# ProPrj___2026-01-25.net
KiCad netlist of a schematic drawn in EasyEDA Pro
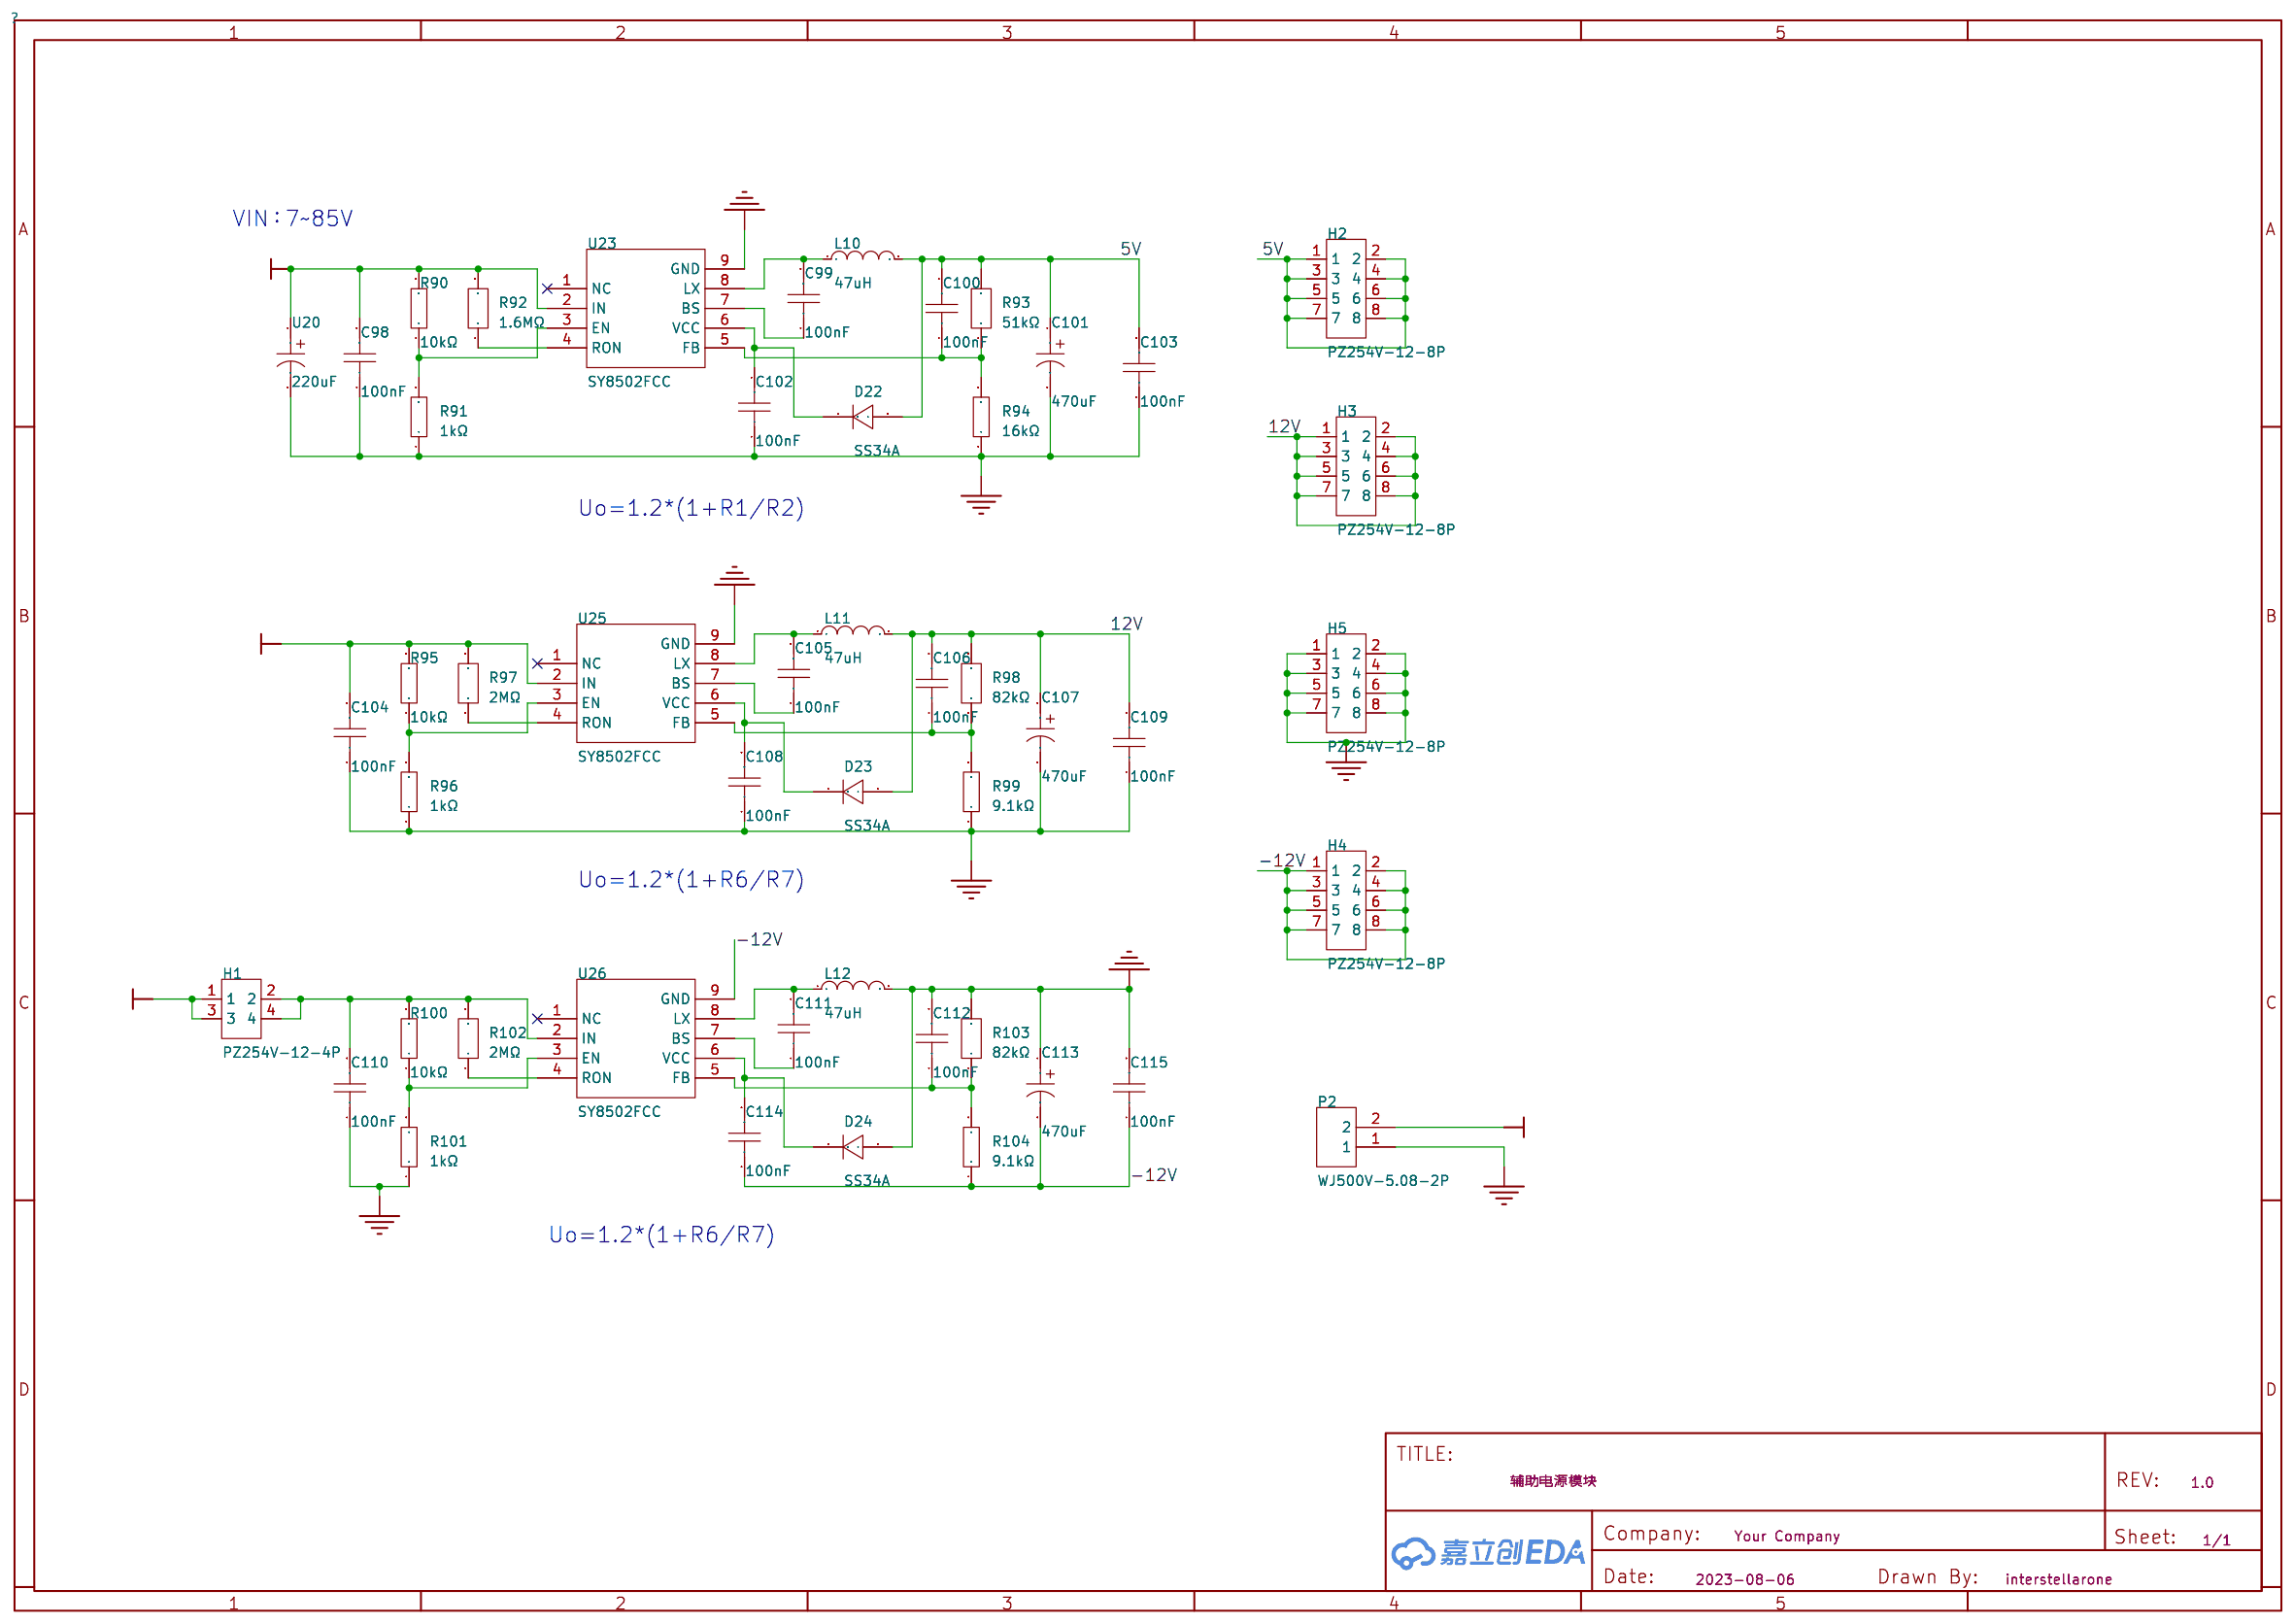
[diagram p0: schematic sheet]

(export (version "E")
  (design (tool "Eeschema 10.0.6"))
  (components
    (comp (ref "C98")
      (value "100nF")
      (footprint "easyedapro:C0603")
      (description "容值:100nF;精度:±10%;额定电压:50V;温度系数:X7R;")
      (fields
        (field (name "Manufacturer Part") "CGA0603X7R104K500JT")
        (field (name "Manufacturer") "HRE(芯声)")
      )
      (libsource (lib "easyedapro") (part "CGA0603X7R104K500JT"))
    )
    (comp (ref "C99")
      (value "100nF")
      (footprint "easyedapro:C0603")
      (description "容值:100nF;精度:±10%;额定电压:50V;温度系数:X7R;")
      (fields
        (field (name "Manufacturer Part") "CGA0603X7R104K500JT")
        (field (name "Manufacturer") "HRE(芯声)")
      )
      (libsource (lib "easyedapro") (part "CGA0603X7R104K500JT"))
    )
    (comp (ref "C100")
      (value "100nF")
      (footprint "easyedapro:C0603")
      (description "容值:100nF;精度:±10%;额定电压:50V;温度系数:X7R;")
      (fields
        (field (name "Manufacturer Part") "CGA0603X7R104K500JT")
        (field (name "Manufacturer") "HRE(芯声)")
      )
      (libsource (lib "easyedapro") (part "CGA0603X7R104K500JT"))
    )
    (comp (ref "C101")
      (value "470uF")
      (footprint "easyedapro:CAP-TH_BD6.0-P2.50-D0.5-FD")
      (description "容值:470uF;额定电压:10V;")
      (fields
        (field (name "Manufacturer Part") "CD110477M1A0607VFL")
        (field (name "Manufacturer") "HRK(鸿瑞凯电子)")
      )
      (libsource (lib "easyedapro") (part "CD110477M1A0607VFL"))
    )
    (comp (ref "C102")
      (value "100nF")
      (footprint "easyedapro:C0603")
      (description "容值:100nF;精度:±10%;额定电压:50V;温度系数:X7R;")
      (fields
        (field (name "Manufacturer Part") "CGA0603X7R104K500JT")
        (field (name "Manufacturer") "HRE(芯声)")
      )
      (libsource (lib "easyedapro") (part "CGA0603X7R104K500JT"))
    )
    (comp (ref "C103")
      (value "100nF")
      (footprint "easyedapro:C0603")
      (description "容值:100nF;精度:±10%;额定电压:50V;温度系数:X7R;")
      (fields
        (field (name "Manufacturer Part") "CGA0603X7R104K500JT")
        (field (name "Manufacturer") "HRE(芯声)")
      )
      (libsource (lib "easyedapro") (part "CGA0603X7R104K500JT"))
    )
    (comp (ref "C104")
      (value "100nF")
      (footprint "easyedapro:C0603")
      (description "容值:100nF;精度:±10%;额定电压:50V;温度系数:X7R;")
      (fields
        (field (name "Manufacturer Part") "CGA0603X7R104K500JT")
        (field (name "Manufacturer") "HRE(芯声)")
      )
      (libsource (lib "easyedapro") (part "CGA0603X7R104K500JT"))
    )
    (comp (ref "C105")
      (value "100nF")
      (footprint "easyedapro:C0603")
      (description "容值:100nF;精度:±10%;额定电压:50V;温度系数:X7R;")
      (fields
        (field (name "Manufacturer Part") "CGA0603X7R104K500JT")
        (field (name "Manufacturer") "HRE(芯声)")
      )
      (libsource (lib "easyedapro") (part "CGA0603X7R104K500JT"))
    )
    (comp (ref "C106")
      (value "100nF")
      (footprint "easyedapro:C0603")
      (description "容值:100nF;精度:±10%;额定电压:50V;温度系数:X7R;")
      (fields
        (field (name "Manufacturer Part") "CGA0603X7R104K500JT")
        (field (name "Manufacturer") "HRE(芯声)")
      )
      (libsource (lib "easyedapro") (part "CGA0603X7R104K500JT"))
    )
    (comp (ref "C107")
      (value "470uF")
      (footprint "easyedapro:CAP-TH_BD6.0-P2.50-D0.5-FD")
      (description "容值:470uF;额定电压:10V;")
      (fields
        (field (name "Manufacturer Part") "CD110477M1A0607VFL")
        (field (name "Manufacturer") "HRK(鸿瑞凯电子)")
      )
      (libsource (lib "easyedapro") (part "CD110477M1A0607VFL"))
    )
    (comp (ref "C108")
      (value "100nF")
      (footprint "easyedapro:C0603")
      (description "容值:100nF;精度:±10%;额定电压:50V;温度系数:X7R;")
      (fields
        (field (name "Manufacturer Part") "CGA0603X7R104K500JT")
        (field (name "Manufacturer") "HRE(芯声)")
      )
      (libsource (lib "easyedapro") (part "CGA0603X7R104K500JT"))
    )
    (comp (ref "C109")
      (value "100nF")
      (footprint "easyedapro:C0603")
      (description "容值:100nF;精度:±10%;额定电压:50V;温度系数:X7R;")
      (fields
        (field (name "Manufacturer Part") "CGA0603X7R104K500JT")
        (field (name "Manufacturer") "HRE(芯声)")
      )
      (libsource (lib "easyedapro") (part "CGA0603X7R104K500JT"))
    )
    (comp (ref "C110")
      (value "100nF")
      (footprint "easyedapro:C0603")
      (description "容值:100nF;精度:±10%;额定电压:50V;温度系数:X7R;")
      (fields
        (field (name "Manufacturer Part") "CGA0603X7R104K500JT")
        (field (name "Manufacturer") "HRE(芯声)")
      )
      (libsource (lib "easyedapro") (part "CGA0603X7R104K500JT"))
    )
    (comp (ref "C111")
      (value "100nF")
      (footprint "easyedapro:C0603")
      (description "容值:100nF;精度:±10%;额定电压:50V;温度系数:X7R;")
      (fields
        (field (name "Manufacturer Part") "CGA0603X7R104K500JT")
        (field (name "Manufacturer") "HRE(芯声)")
      )
      (libsource (lib "easyedapro") (part "CGA0603X7R104K500JT"))
    )
    (comp (ref "C112")
      (value "100nF")
      (footprint "easyedapro:C0603")
      (description "容值:100nF;精度:±10%;额定电压:50V;温度系数:X7R;")
      (fields
        (field (name "Manufacturer Part") "CGA0603X7R104K500JT")
        (field (name "Manufacturer") "HRE(芯声)")
      )
      (libsource (lib "easyedapro") (part "CGA0603X7R104K500JT"))
    )
    (comp (ref "C113")
      (value "470uF")
      (footprint "easyedapro:CAP-TH_BD6.0-P2.50-D0.5-FD")
      (description "容值:470uF;额定电压:10V;")
      (fields
        (field (name "Manufacturer Part") "CD110477M1A0607VFL")
        (field (name "Manufacturer") "HRK(鸿瑞凯电子)")
      )
      (libsource (lib "easyedapro") (part "CD110477M1A0607VFL"))
    )
    (comp (ref "C114")
      (value "100nF")
      (footprint "easyedapro:C0603")
      (description "容值:100nF;精度:±10%;额定电压:50V;温度系数:X7R;")
      (fields
        (field (name "Manufacturer Part") "CGA0603X7R104K500JT")
        (field (name "Manufacturer") "HRE(芯声)")
      )
      (libsource (lib "easyedapro") (part "CGA0603X7R104K500JT"))
    )
    (comp (ref "C115")
      (value "100nF")
      (footprint "easyedapro:C0603")
      (description "容值:100nF;精度:±10%;额定电压:50V;温度系数:X7R;")
      (fields
        (field (name "Manufacturer Part") "CGA0603X7R104K500JT")
        (field (name "Manufacturer") "HRE(芯声)")
      )
      (libsource (lib "easyedapro") (part "CGA0603X7R104K500JT"))
    )
    (comp (ref "D22")
      (value "SS34A")
      (footprint "easyedapro:SMA_L4.3-W2.6-LS5.2-RD")
      (description "正向压降(Vf):500mV@3A;直流反向耐压(Vr):40V;整流电流:3A;")
      (fields (field (name "Manufacturer") "YANGJIE(扬杰)"))
      (libsource (lib "easyedapro") (part "SS34A"))
    )
    (comp (ref "D23")
      (value "SS34A")
      (footprint "easyedapro:SMA_L4.3-W2.6-LS5.2-RD")
      (description "正向压降(Vf):500mV@3A;直流反向耐压(Vr):40V;整流电流:3A;")
      (fields (field (name "Manufacturer") "YANGJIE(扬杰)"))
      (libsource (lib "easyedapro") (part "SS34A"))
    )
    (comp (ref "D24")
      (value "SS34A")
      (footprint "easyedapro:SMA_L4.3-W2.6-LS5.2-RD")
      (description "正向压降(Vf):500mV@3A;直流反向耐压(Vr):40V;整流电流:3A;")
      (fields (field (name "Manufacturer") "YANGJIE(扬杰)"))
      (libsource (lib "easyedapro") (part "SS34A"))
    )
    (comp (ref "H1")
      (value "PZ254V-12-4P")
      (footprint "easyedapro:HDR-TH_4P-P2.54-V-M-R2-C2-S2.54")
      (fields (field (name "Manufacturer") "XFCN(兴飞)"))
      (libsource (lib "easyedapro") (part "PZ254V-12-4P"))
    )
    (comp (ref "H2")
      (value "PZ254V-12-8P")
      (footprint "easyedapro:HDR-TH_8P-P2.54-V-M-R2-C4-S2.54")
      (fields (field (name "Manufacturer") "XFCN(兴飞)"))
      (libsource (lib "easyedapro") (part "PZ254V-12-8P"))
    )
    (comp (ref "H3")
      (value "PZ254V-12-8P")
      (footprint "easyedapro:HDR-TH_8P-P2.54-V-M-R2-C4-S2.54")
      (fields (field (name "Manufacturer") "XFCN(兴飞)"))
      (libsource (lib "easyedapro") (part "PZ254V-12-8P"))
    )
    (comp (ref "H4")
      (value "PZ254V-12-8P")
      (footprint "easyedapro:HDR-TH_8P-P2.54-V-M-R2-C4-S2.54")
      (fields (field (name "Manufacturer") "XFCN(兴飞)"))
      (libsource (lib "easyedapro") (part "PZ254V-12-8P"))
    )
    (comp (ref "H5")
      (value "PZ254V-12-8P")
      (footprint "easyedapro:HDR-TH_8P-P2.54-V-M-R2-C4-S2.54")
      (fields (field (name "Manufacturer") "XFCN(兴飞)"))
      (libsource (lib "easyedapro") (part "PZ254V-12-8P"))
    )
    (comp (ref "L10")
      (value "47uH")
      (footprint "easyedapro:IND-SMD_L7.0-W6.6_FXL0630")
      (description "电感值:47uH;精度:±20%;额定电流:1.5A;饱和电流(Isat):2A;类型:一体成型电感;")
      (fields (field (name "Manufacturer Part") "FXL0630-470-M") (field (name "Manufacturer") "cjiang(长江微电)"))
      (libsource (lib "easyedapro") (part "FXL0630-470-M"))
    )
    (comp (ref "L11")
      (value "47uH")
      (footprint "easyedapro:IND-SMD_L7.0-W6.6_FXL0630")
      (description "电感值:47uH;精度:±20%;额定电流:1.5A;饱和电流(Isat):2A;类型:一体成型电感;")
      (fields (field (name "Manufacturer Part") "FXL0630-470-M") (field (name "Manufacturer") "cjiang(长江微电)"))
      (libsource (lib "easyedapro") (part "FXL0630-470-M"))
    )
    (comp (ref "L12")
      (value "47uH")
      (footprint "easyedapro:IND-SMD_L7.0-W6.6_FXL0630")
      (description "电感值:47uH;精度:±20%;额定电流:1.5A;饱和电流(Isat):2A;类型:一体成型电感;")
      (fields (field (name "Manufacturer Part") "FXL0630-470-M") (field (name "Manufacturer") "cjiang(长江微电)"))
      (libsource (lib "easyedapro") (part "FXL0630-470-M"))
    )
    (comp (ref "P2")
      (value "WJ500V-5.08-2P")
      (footprint "easyedapro:CONN-TH_2P-P5.00_WJ500V-5.08-2P")
      (fields (field (name "Manufacturer") "KANGNEX(康奈克斯电气)"))
      (libsource (lib "easyedapro") (part "WJ500V-5.08-2P-14-00A"))
    )
    (comp (ref "R90")
      (value "10kΩ")
      (footprint "easyedapro:R0603")
      (description "电阻类型:厚膜电阻;阻值:10kΩ;精度:±1%;功率:100mW;最大工作电压:75V;温度系数:±100ppm/°C;")
      (fields
        (field (name "Manufacturer Part") "0603WAF1002T5E")
        (field (name "Manufacturer") "UNI-ROYAL(厚声)")
      )
      (libsource (lib "easyedapro") (part "0603WAF1002T5E"))
    )
    (comp (ref "R91")
      (value "1kΩ")
      (footprint "easyedapro:R0603")
      (description "电阻类型:厚膜电阻;阻值:1kΩ;精度:±1%;功率:100mW;最大工作电压:75V;温度系数:±100ppm/°C;")
      (fields
        (field (name "Manufacturer Part") "0603WAF1001T5E")
        (field (name "Manufacturer") "UNI-ROYAL(厚声)")
      )
      (libsource (lib "easyedapro") (part "0603WAF1001T5E"))
    )
    (comp (ref "R92")
      (value "1.6MΩ")
      (footprint "easyedapro:R0603")
      (description "电阻类型:厚膜电阻;阻值:1.6MΩ;精度:±5%;功率:100mW;最大工作电压:75V;温度系数:±100ppm/°C;")
      (fields (field (name "Manufacturer Part") "FRC0603J165 TS") (field (name "Manufacturer") "FOJAN(富捷)"))
      (libsource (lib "easyedapro") (part "FRC0603J165 TS"))
    )
    (comp (ref "R93")
      (value "51kΩ")
      (footprint "easyedapro:R0603")
      (description "电阻类型:厚膜电阻;阻值:51kΩ;精度:±1%;功率:100mW;最大工作电压:75V;温度系数:±100ppm/°C;")
      (fields (field (name "Manufacturer Part") "FRC0603F5102TS") (field (name "Manufacturer") "FOJAN(富捷)"))
      (libsource (lib "easyedapro") (part "FRC0603F5102TS"))
    )
    (comp (ref "R94")
      (value "16kΩ")
      (footprint "easyedapro:R0603")
      (description "电阻类型:厚膜电阻;阻值:16kΩ;精度:±1%;功率:100mW;最大工作电压:75V;温度系数:±100ppm/°C;")
      (fields
        (field (name "Manufacturer Part") "0603WAF1602T5E")
        (field (name "Manufacturer") "UNI-ROYAL(厚声)")
      )
      (libsource (lib "easyedapro") (part "16KΩ(1602) ±1%"))
    )
    (comp (ref "R95")
      (value "10kΩ")
      (footprint "easyedapro:R0603")
      (description "电阻类型:厚膜电阻;阻值:10kΩ;精度:±1%;功率:100mW;最大工作电压:75V;温度系数:±100ppm/°C;")
      (fields
        (field (name "Manufacturer Part") "0603WAF1002T5E")
        (field (name "Manufacturer") "UNI-ROYAL(厚声)")
      )
      (libsource (lib "easyedapro") (part "0603WAF1002T5E"))
    )
    (comp (ref "R96")
      (value "1kΩ")
      (footprint "easyedapro:R0603")
      (description "电阻类型:厚膜电阻;阻值:1kΩ;精度:±1%;功率:100mW;最大工作电压:75V;温度系数:±100ppm/°C;")
      (fields
        (field (name "Manufacturer Part") "0603WAF1001T5E")
        (field (name "Manufacturer") "UNI-ROYAL(厚声)")
      )
      (libsource (lib "easyedapro") (part "0603WAF1001T5E"))
    )
    (comp (ref "R97")
      (value "2MΩ")
      (footprint "easyedapro:R0603")
      (description "电阻类型:厚膜电阻;阻值:1.6MΩ;精度:±5%;功率:100mW;最大工作电压:75V;温度系数:±100ppm/°C;")
      (fields (field (name "Manufacturer Part") "FRC0603J165 TS") (field (name "Manufacturer") "FOJAN(富捷)"))
      (libsource (lib "easyedapro") (part "FRC0603J165 TS"))
    )
    (comp (ref "R98")
      (value "82kΩ")
      (footprint "easyedapro:R0603")
      (description "电阻类型:厚膜电阻;阻值:51kΩ;精度:±1%;功率:100mW;最大工作电压:75V;温度系数:±100ppm/°C;")
      (fields (field (name "Manufacturer Part") "FRC0603F5102TS") (field (name "Manufacturer") "FOJAN(富捷)"))
      (libsource (lib "easyedapro") (part "FRC0603F5102TS"))
    )
    (comp (ref "R99")
      (value "9.1kΩ")
      (footprint "easyedapro:R0603")
      (description "电阻类型:厚膜电阻;阻值:16kΩ;精度:±1%;功率:100mW;最大工作电压:75V;温度系数:±100ppm/°C;")
      (fields
        (field (name "Manufacturer Part") "0603WAF1602T5E")
        (field (name "Manufacturer") "UNI-ROYAL(厚声)")
      )
      (libsource (lib "easyedapro") (part "16KΩ(1602) ±1%"))
    )
    (comp (ref "R100")
      (value "10kΩ")
      (footprint "easyedapro:R0603")
      (description "电阻类型:厚膜电阻;阻值:10kΩ;精度:±1%;功率:100mW;最大工作电压:75V;温度系数:±100ppm/°C;")
      (fields
        (field (name "Manufacturer Part") "0603WAF1002T5E")
        (field (name "Manufacturer") "UNI-ROYAL(厚声)")
      )
      (libsource (lib "easyedapro") (part "0603WAF1002T5E"))
    )
    (comp (ref "R101")
      (value "1kΩ")
      (footprint "easyedapro:R0603")
      (description "电阻类型:厚膜电阻;阻值:1kΩ;精度:±1%;功率:100mW;最大工作电压:75V;温度系数:±100ppm/°C;")
      (fields
        (field (name "Manufacturer Part") "0603WAF1001T5E")
        (field (name "Manufacturer") "UNI-ROYAL(厚声)")
      )
      (libsource (lib "easyedapro") (part "0603WAF1001T5E"))
    )
    (comp (ref "R102")
      (value "2MΩ")
      (footprint "easyedapro:R0603")
      (description "电阻类型:厚膜电阻;阻值:1.6MΩ;精度:±5%;功率:100mW;最大工作电压:75V;温度系数:±100ppm/°C;")
      (fields (field (name "Manufacturer Part") "FRC0603J165 TS") (field (name "Manufacturer") "FOJAN(富捷)"))
      (libsource (lib "easyedapro") (part "FRC0603J165 TS"))
    )
    (comp (ref "R103")
      (value "82kΩ")
      (footprint "easyedapro:R0603")
      (description "电阻类型:厚膜电阻;阻值:51kΩ;精度:±1%;功率:100mW;最大工作电压:75V;温度系数:±100ppm/°C;")
      (fields (field (name "Manufacturer Part") "FRC0603F5102TS") (field (name "Manufacturer") "FOJAN(富捷)"))
      (libsource (lib "easyedapro") (part "FRC0603F5102TS"))
    )
    (comp (ref "R104")
      (value "9.1kΩ")
      (footprint "easyedapro:R0603")
      (description "电阻类型:厚膜电阻;阻值:16kΩ;精度:±1%;功率:100mW;最大工作电压:75V;温度系数:±100ppm/°C;")
      (fields
        (field (name "Manufacturer Part") "0603WAF1602T5E")
        (field (name "Manufacturer") "UNI-ROYAL(厚声)")
      )
      (libsource (lib "easyedapro") (part "16KΩ(1602) ±1%"))
    )
    (comp (ref "U20")
      (value "220uF")
      (footprint "easyedapro:CAP-TH_BD12.5-P5.00-D0.6-FD")
      (description "容值:220uF;精度:±20%;额定电压:100V;")
      (fields (field (name "Manufacturer Part") "ERJ1KM221W20OT") (field (name "Manufacturer") "AISHI(艾华集团)"))
      (libsource (lib "easyedapro") (part "ERJ1KM221W20OT"))
    )
    (comp (ref "U23")
      (value "SY8502FCC")
      (footprint "easyedapro:SOIC-8_L4.9-W3.9-P1.27-LS6.0-BL-EP")
      (description "功能类型:降压型;输出类型:固定;工作电压:7V~85V;输出电压:5V;输出电流:1.2A;")
      (fields (field (name "Manufacturer") "silergy(矽力杰)"))
      (libsource (lib "easyedapro") (part "SY8502FCC"))
    )
    (comp (ref "U25")
      (value "SY8502FCC")
      (footprint "easyedapro:SOIC-8_L4.9-W3.9-P1.27-LS6.0-BL-EP")
      (description "功能类型:降压型;输出类型:固定;工作电压:7V~85V;输出电压:5V;输出电流:1.2A;")
      (fields (field (name "Manufacturer") "silergy(矽力杰)"))
      (libsource (lib "easyedapro") (part "SY8502FCC"))
    )
    (comp (ref "U26")
      (value "SY8502FCC")
      (footprint "easyedapro:SOIC-8_L4.9-W3.9-P1.27-LS6.0-BL-EP")
      (description "功能类型:降压型;输出类型:固定;工作电压:7V~85V;输出电压:5V;输出电流:1.2A;")
      (fields (field (name "Manufacturer") "silergy(矽力杰)"))
      (libsource (lib "easyedapro") (part "SY8502FCC"))
    )
  )
  (nets
    (net (code "1") (name "/-12V") (class "Default")
      (node (ref "C113") (pin "2") (pinfunction "2_2") (pintype "input"))
      (node (ref "C114") (pin "1") (pinfunction "1_1") (pintype "unspecified"))
      (node (ref "C115") (pin "1") (pinfunction "1_1") (pintype "unspecified"))
      (node (ref "H4") (pin "1") (pinfunction "1_1") (pintype "unspecified"))
      (node (ref "H4") (pin "2") (pinfunction "2_2") (pintype "unspecified"))
      (node (ref "H4") (pin "3") (pinfunction "3_3") (pintype "unspecified"))
      (node (ref "H4") (pin "4") (pinfunction "4_4") (pintype "unspecified"))
      (node (ref "H4") (pin "5") (pinfunction "5_5") (pintype "unspecified"))
      (node (ref "H4") (pin "6") (pinfunction "6_6") (pintype "unspecified"))
      (node (ref "H4") (pin "7") (pinfunction "7_7") (pintype "unspecified"))
      (node (ref "H4") (pin "8") (pinfunction "8_8") (pintype "unspecified"))
      (node (ref "R104") (pin "1") (pinfunction "1_1") (pintype "unspecified"))
      (node (ref "U26") (pin "9") (pinfunction "GND_9") (pintype "unspecified"))
    )
    (net (code "2") (name "/5V") (class "Default")
      (node (ref "C100") (pin "2") (pinfunction "2_2") (pintype "unspecified"))
      (node (ref "C101") (pin "1") (pinfunction "1_1") (pintype "input"))
      (node (ref "C103") (pin "2") (pinfunction "2_2") (pintype "unspecified"))
      (node (ref "D22") (pin "2") (pinfunction "A_2") (pintype "unspecified"))
      (node (ref "H2") (pin "1") (pinfunction "1_1") (pintype "unspecified"))
      (node (ref "H2") (pin "2") (pinfunction "2_2") (pintype "unspecified"))
      (node (ref "H2") (pin "3") (pinfunction "3_3") (pintype "unspecified"))
      (node (ref "H2") (pin "4") (pinfunction "4_4") (pintype "unspecified"))
      (node (ref "H2") (pin "5") (pinfunction "5_5") (pintype "unspecified"))
      (node (ref "H2") (pin "6") (pinfunction "6_6") (pintype "unspecified"))
      (node (ref "H2") (pin "7") (pinfunction "7_7") (pintype "unspecified"))
      (node (ref "H2") (pin "8") (pinfunction "8_8") (pintype "unspecified"))
      (node (ref "L10") (pin "2") (pinfunction "2_2") (pintype "unspecified"))
      (node (ref "R93") (pin "2") (pinfunction "2_2") (pintype "unspecified"))
    )
    (net (code "3") (name "/12V") (class "Default")
      (node (ref "C106") (pin "2") (pinfunction "2_2") (pintype "unspecified"))
      (node (ref "C107") (pin "1") (pinfunction "1_1") (pintype "input"))
      (node (ref "C109") (pin "2") (pinfunction "2_2") (pintype "unspecified"))
      (node (ref "D23") (pin "2") (pinfunction "A_2") (pintype "unspecified"))
      (node (ref "H3") (pin "1") (pinfunction "1_1") (pintype "unspecified"))
      (node (ref "H3") (pin "2") (pinfunction "2_2") (pintype "unspecified"))
      (node (ref "H3") (pin "3") (pinfunction "3_3") (pintype "unspecified"))
      (node (ref "H3") (pin "4") (pinfunction "4_4") (pintype "unspecified"))
      (node (ref "H3") (pin "5") (pinfunction "5_5") (pintype "unspecified"))
      (node (ref "H3") (pin "6") (pinfunction "6_6") (pintype "unspecified"))
      (node (ref "H3") (pin "7") (pinfunction "7_7") (pintype "unspecified"))
      (node (ref "H3") (pin "8") (pinfunction "8_8") (pintype "unspecified"))
      (node (ref "L11") (pin "2") (pinfunction "2_2") (pintype "unspecified"))
      (node (ref "R98") (pin "2") (pinfunction "2_2") (pintype "unspecified"))
    )
    (net (code "4") (name "GND") (class "Default")
      (node (ref "C101") (pin "2") (pinfunction "2_2") (pintype "input"))
      (node (ref "C102") (pin "1") (pinfunction "1_1") (pintype "unspecified"))
      (node (ref "C103") (pin "1") (pinfunction "1_1") (pintype "unspecified"))
      (node (ref "C104") (pin "1") (pinfunction "1_1") (pintype "unspecified"))
      (node (ref "C107") (pin "2") (pinfunction "2_2") (pintype "input"))
      (node (ref "C108") (pin "1") (pinfunction "1_1") (pintype "unspecified"))
      (node (ref "C109") (pin "1") (pinfunction "1_1") (pintype "unspecified"))
      (node (ref "C110") (pin "1") (pinfunction "1_1") (pintype "unspecified"))
      (node (ref "C112") (pin "2") (pinfunction "2_2") (pintype "unspecified"))
      (node (ref "C113") (pin "1") (pinfunction "1_1") (pintype "input"))
      (node (ref "C115") (pin "2") (pinfunction "2_2") (pintype "unspecified"))
      (node (ref "C98") (pin "1") (pinfunction "1_1") (pintype "unspecified"))
      (node (ref "D24") (pin "2") (pinfunction "A_2") (pintype "unspecified"))
      (node (ref "H5") (pin "1") (pinfunction "1_1") (pintype "unspecified"))
      (node (ref "H5") (pin "2") (pinfunction "2_2") (pintype "unspecified"))
      (node (ref "H5") (pin "3") (pinfunction "3_3") (pintype "unspecified"))
      (node (ref "H5") (pin "4") (pinfunction "4_4") (pintype "unspecified"))
      (node (ref "H5") (pin "5") (pinfunction "5_5") (pintype "unspecified"))
      (node (ref "H5") (pin "6") (pinfunction "6_6") (pintype "unspecified"))
      (node (ref "H5") (pin "7") (pinfunction "7_7") (pintype "unspecified"))
      (node (ref "H5") (pin "8") (pinfunction "8_8") (pintype "unspecified"))
      (node (ref "L12") (pin "2") (pinfunction "2_2") (pintype "unspecified"))
      (node (ref "P2") (pin "1") (pinfunction "1_1") (pintype "unspecified"))
      (node (ref "R101") (pin "1") (pinfunction "1_1") (pintype "input"))
      (node (ref "R103") (pin "2") (pinfunction "2_2") (pintype "unspecified"))
      (node (ref "R91") (pin "1") (pinfunction "1_1") (pintype "input"))
      (node (ref "R94") (pin "1") (pinfunction "1_1") (pintype "unspecified"))
      (node (ref "R96") (pin "1") (pinfunction "1_1") (pintype "input"))
      (node (ref "R99") (pin "1") (pinfunction "1_1") (pintype "unspecified"))
      (node (ref "U20") (pin "2") (pinfunction "2_2") (pintype "input"))
      (node (ref "U23") (pin "9") (pinfunction "GND_9") (pintype "unspecified"))
      (node (ref "U25") (pin "9") (pinfunction "GND_9") (pintype "unspecified"))
    )
    (net (code "5") (name "Net-(D22-C)") (class "Default")
      (node (ref "C102") (pin "2") (pinfunction "2_2") (pintype "unspecified"))
      (node (ref "D22") (pin "1") (pinfunction "C_1") (pintype "unspecified"))
      (node (ref "U23") (pin "6") (pinfunction "VCC_6") (pintype "unspecified"))
    )
    (net (code "6") (name "Net-(D23-C)") (class "Default")
      (node (ref "C108") (pin "2") (pinfunction "2_2") (pintype "unspecified"))
      (node (ref "D23") (pin "1") (pinfunction "C_1") (pintype "unspecified"))
      (node (ref "U25") (pin "6") (pinfunction "VCC_6") (pintype "unspecified"))
    )
    (net (code "7") (name "Net-(D24-C)") (class "Default")
      (node (ref "C114") (pin "2") (pinfunction "2_2") (pintype "unspecified"))
      (node (ref "D24") (pin "1") (pinfunction "C_1") (pintype "unspecified"))
      (node (ref "U26") (pin "6") (pinfunction "VCC_6") (pintype "unspecified"))
    )
    (net (code "8") (name "Net-(U23-BS)") (class "Default")
      (node (ref "C99") (pin "1") (pinfunction "1_1") (pintype "unspecified"))
      (node (ref "U23") (pin "7") (pinfunction "BS_7") (pintype "unspecified"))
    )
    (net (code "9") (name "Net-(U23-EN)") (class "Default")
      (node (ref "R90") (pin "1") (pinfunction "1_1") (pintype "input"))
      (node (ref "R91") (pin "2") (pinfunction "2_2") (pintype "input"))
      (node (ref "U23") (pin "3") (pinfunction "EN_3") (pintype "unspecified"))
    )
    (net (code "10") (name "Net-(U23-FB)") (class "Default")
      (node (ref "C100") (pin "1") (pinfunction "1_1") (pintype "unspecified"))
      (node (ref "R93") (pin "1") (pinfunction "1_1") (pintype "unspecified"))
      (node (ref "R94") (pin "2") (pinfunction "2_2") (pintype "unspecified"))
      (node (ref "U23") (pin "5") (pinfunction "FB_5") (pintype "unspecified"))
    )
    (net (code "11") (name "Net-(U23-LX)") (class "Default")
      (node (ref "C99") (pin "2") (pinfunction "2_2") (pintype "unspecified"))
      (node (ref "L10") (pin "1") (pinfunction "1_1") (pintype "unspecified"))
      (node (ref "U23") (pin "8") (pinfunction "LX_8") (pintype "unspecified"))
    )
    (net (code "12") (name "Net-(U23-RON)") (class "Default")
      (node (ref "R92") (pin "1") (pinfunction "1_1") (pintype "unspecified"))
      (node (ref "U23") (pin "4") (pinfunction "RON_4") (pintype "unspecified"))
    )
    (net (code "13") (name "Net-(U25-BS)") (class "Default")
      (node (ref "C105") (pin "1") (pinfunction "1_1") (pintype "unspecified"))
      (node (ref "U25") (pin "7") (pinfunction "BS_7") (pintype "unspecified"))
    )
    (net (code "14") (name "Net-(U25-EN)") (class "Default")
      (node (ref "R95") (pin "1") (pinfunction "1_1") (pintype "input"))
      (node (ref "R96") (pin "2") (pinfunction "2_2") (pintype "input"))
      (node (ref "U25") (pin "3") (pinfunction "EN_3") (pintype "unspecified"))
    )
    (net (code "15") (name "Net-(U25-FB)") (class "Default")
      (node (ref "C106") (pin "1") (pinfunction "1_1") (pintype "unspecified"))
      (node (ref "R98") (pin "1") (pinfunction "1_1") (pintype "unspecified"))
      (node (ref "R99") (pin "2") (pinfunction "2_2") (pintype "unspecified"))
      (node (ref "U25") (pin "5") (pinfunction "FB_5") (pintype "unspecified"))
    )
    (net (code "16") (name "Net-(U25-LX)") (class "Default")
      (node (ref "C105") (pin "2") (pinfunction "2_2") (pintype "unspecified"))
      (node (ref "L11") (pin "1") (pinfunction "1_1") (pintype "unspecified"))
      (node (ref "U25") (pin "8") (pinfunction "LX_8") (pintype "unspecified"))
    )
    (net (code "17") (name "Net-(U25-RON)") (class "Default")
      (node (ref "R97") (pin "1") (pinfunction "1_1") (pintype "unspecified"))
      (node (ref "U25") (pin "4") (pinfunction "RON_4") (pintype "unspecified"))
    )
    (net (code "18") (name "Net-(U26-BS)") (class "Default")
      (node (ref "C111") (pin "1") (pinfunction "1_1") (pintype "unspecified"))
      (node (ref "U26") (pin "7") (pinfunction "BS_7") (pintype "unspecified"))
    )
    (net (code "19") (name "Net-(U26-EN)") (class "Default")
      (node (ref "R100") (pin "1") (pinfunction "1_1") (pintype "input"))
      (node (ref "R101") (pin "2") (pinfunction "2_2") (pintype "input"))
      (node (ref "U26") (pin "3") (pinfunction "EN_3") (pintype "unspecified"))
    )
    (net (code "20") (name "Net-(U26-FB)") (class "Default")
      (node (ref "C112") (pin "1") (pinfunction "1_1") (pintype "unspecified"))
      (node (ref "R103") (pin "1") (pinfunction "1_1") (pintype "unspecified"))
      (node (ref "R104") (pin "2") (pinfunction "2_2") (pintype "unspecified"))
      (node (ref "U26") (pin "5") (pinfunction "FB_5") (pintype "unspecified"))
    )
    (net (code "21") (name "Net-(U26-IN)") (class "Default")
      (node (ref "C110") (pin "2") (pinfunction "2_2") (pintype "unspecified"))
      (node (ref "H1") (pin "2") (pinfunction "2_2") (pintype "unspecified"))
      (node (ref "H1") (pin "4") (pinfunction "4_4") (pintype "unspecified"))
      (node (ref "R100") (pin "2") (pinfunction "2_2") (pintype "input"))
      (node (ref "R102") (pin "2") (pinfunction "2_2") (pintype "unspecified"))
      (node (ref "U26") (pin "2") (pinfunction "IN_2") (pintype "unspecified"))
    )
    (net (code "22") (name "Net-(U26-LX)") (class "Default")
      (node (ref "C111") (pin "2") (pinfunction "2_2") (pintype "unspecified"))
      (node (ref "L12") (pin "1") (pinfunction "1_1") (pintype "unspecified"))
      (node (ref "U26") (pin "8") (pinfunction "LX_8") (pintype "unspecified"))
    )
    (net (code "23") (name "Net-(U26-RON)") (class "Default")
      (node (ref "R102") (pin "1") (pinfunction "1_1") (pintype "unspecified"))
      (node (ref "U26") (pin "4") (pinfunction "RON_4") (pintype "unspecified"))
    )
    (net (code "24") (name "VCC") (class "Default")
      (node (ref "C104") (pin "2") (pinfunction "2_2") (pintype "unspecified"))
      (node (ref "C98") (pin "2") (pinfunction "2_2") (pintype "unspecified"))
      (node (ref "H1") (pin "1") (pinfunction "1_1") (pintype "unspecified"))
      (node (ref "H1") (pin "3") (pinfunction "3_3") (pintype "unspecified"))
      (node (ref "P2") (pin "2") (pinfunction "2_2") (pintype "unspecified"))
      (node (ref "R90") (pin "2") (pinfunction "2_2") (pintype "input"))
      (node (ref "R92") (pin "2") (pinfunction "2_2") (pintype "unspecified"))
      (node (ref "R95") (pin "2") (pinfunction "2_2") (pintype "input"))
      (node (ref "R97") (pin "2") (pinfunction "2_2") (pintype "unspecified"))
      (node (ref "U20") (pin "1") (pinfunction "1_1") (pintype "input"))
      (node (ref "U23") (pin "2") (pinfunction "IN_2") (pintype "unspecified"))
      (node (ref "U25") (pin "2") (pinfunction "IN_2") (pintype "unspecified"))
    )
    (net (code "25") (name "unconnected-(U23-NC-Pad1)") (class "Default")
      (node (ref "U23") (pin "1") (pinfunction "NC_1") (pintype "unspecified+no_connect"))
    )
    (net (code "26") (name "unconnected-(U25-NC-Pad1)") (class "Default")
      (node (ref "U25") (pin "1") (pinfunction "NC_1") (pintype "unspecified+no_connect"))
    )
    (net (code "27") (name "unconnected-(U26-NC-Pad1)") (class "Default")
      (node (ref "U26") (pin "1") (pinfunction "NC_1") (pintype "unspecified+no_connect"))
    )
  )
)
